# Reciever_Schematic.net
KiCad netlist of a schematic drawn in Altium Designer
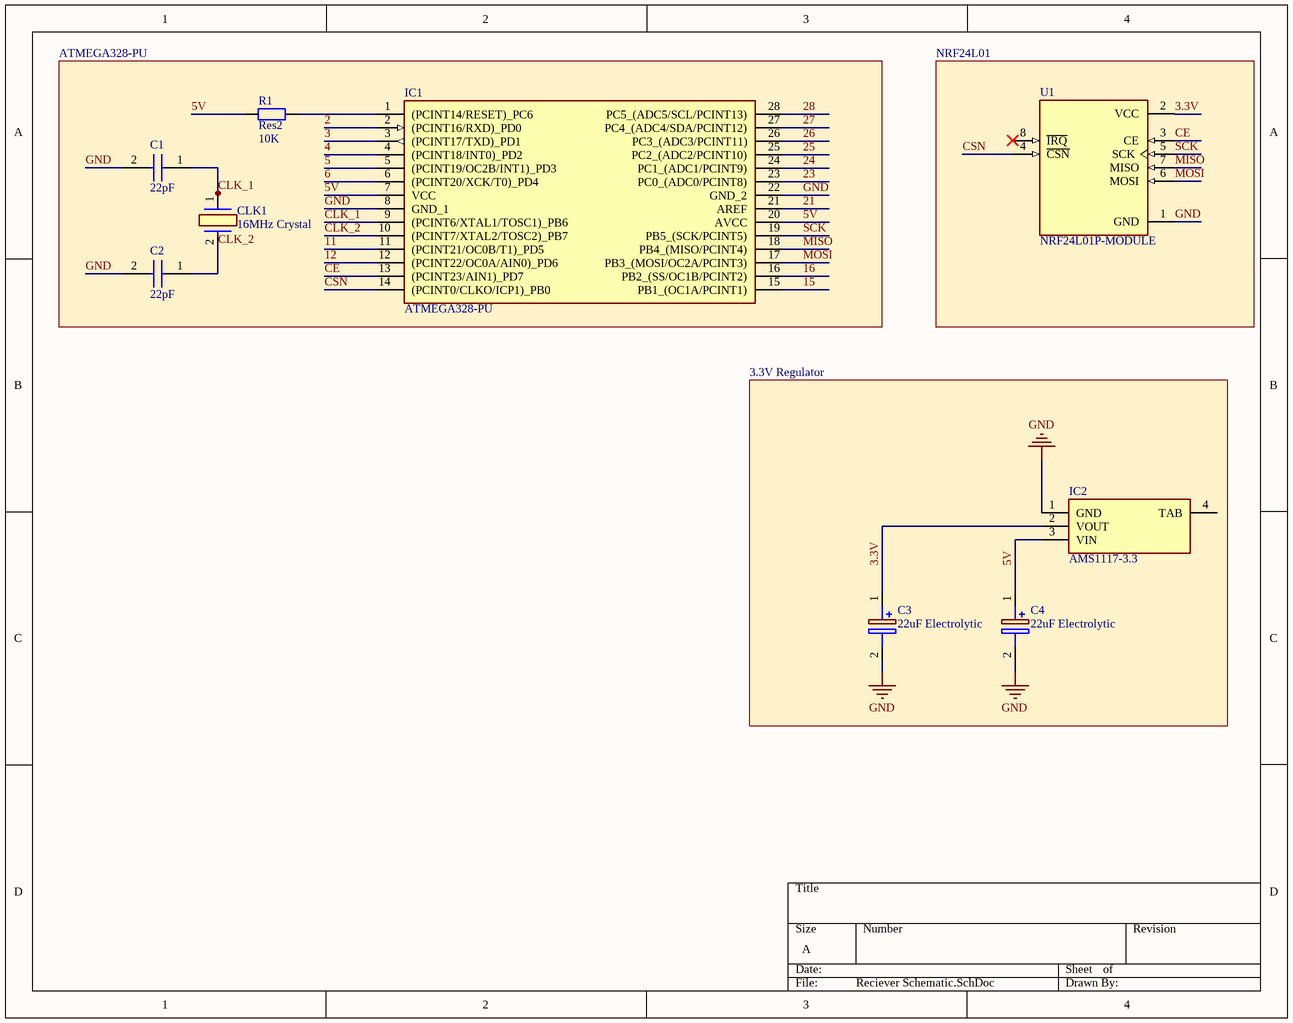
[diagram p0: Reciever Schematic.SchDoc]

(export (version "E")
  (design (tool "Eeschema 10.0.6"))
  (components
    (comp (ref "C1")
      (value "22pF")
      (footprint "SamacSys:S220K25SL0N63L6R")
      (description "Capacitor Ceramic THT")
      (fields
        (field (name "MANUFACTURER_PART_NUMBER") "S220K25SL0N63L6R")
        (field (name "MOUSER PART NUMBER") "594-S220K25SL0N63L6R")
      )
      (libsource (lib "*") (part "S220K25SL0N63L6R"))
    )
    (comp (ref "C2")
      (value "22pF")
      (footprint "SamacSys:S220K25SL0N63L6R")
      (description "Capacitor Ceramic THT")
      (fields
        (field (name "MANUFACTURER_PART_NUMBER") "S220K25SL0N63L6R")
        (field (name "MOUSER PART NUMBER") "594-S220K25SL0N63L6R")
      )
      (libsource (lib "*") (part "S220K25SL0N63L6R"))
    )
    (comp (ref "C3")
      (value "22uF Electrolytic")
      (footprint "SamacSys:CAPPRD250W55D630H1220")
      (description "Capacitor Polarised")
      (fields (field (name "MANUFACTURER_PART_NUMBER") "ECA1EEN220"))
      (libsource (lib "*") (part "ECA1EEN220"))
    )
    (comp (ref "C4")
      (value "22uF Electrolytic")
      (footprint "SamacSys:CAPPRD250W55D630H1220")
      (description "Capacitor Polarised")
      (fields (field (name "MANUFACTURER_PART_NUMBER") "ECA1EEN220"))
      (libsource (lib "*") (part "ECA1EEN220"))
    )
    (comp (ref "CLK1")
      (value "16MHz Crystal")
      (footprint "SamacSys:LFXTAL036391Bulk")
      (description "Crystal or Oscillator")
      (fields
        (field (name "MANUFACTURER_PART_NUMBER") "LFXTAL036391Bulk")
        (field (name "MOUSER PART NUMBER") "449-LFXTAL036391BULK")
      )
      (libsource (lib "*") (part "LFXTAL036391Bulk"))
    )
    (comp (ref "IC1")
      (value "ATMEGA328-PU")
      (footprint "SamacSys:DIP1016W53P254L3468H457Q28N")
      (description "Integrated Circuit")
      (fields (field (name "MOUSER PART NUMBER") "556-ATMEGA328-PU"))
      (libsource (lib "*") (part "ATMEGA328-PU"))
    )
    (comp (ref "IC2")
      (value "AMS1117-3.3")
      (footprint "SamacSys:SOT229P700X180-4N")
      (description "Integrated Circuit")
      (libsource (lib "*") (part "AMS1117-3.3"))
    )
    (comp (ref "R1")
      (value "Res2")
      (footprint "AXIAL-0.4")
      (description "Resistor")
      (fields (field (name "ALTIUM_VALUE") "10K") (field (name "PUBLISHER") "Altium Limited"))
      (libsource (lib "Miscellaneous Devices") (part "Res2"))
    )
    (comp (ref "U1")
      (value "NRF24L01P-MODULE")
      (footprint "XCVR_NRF24L01P-MODULE-PCB")
      (description "- Transceiver For Use With nRF24L01+")
      (fields (field (name "MP") "NRF24L01P-MODULE-PCB") (field (name "MF") "Nordic Semiconductor"))
      (libsource (lib "NRF24L01P-MODULE-PCB") (part "NRF24L01P-MODULE-PCB"))
    )
  )
  (nets
    (net (code "1") (name "/2") (class "Default")
      (node (ref "IC1") (pin "2") (pinfunction "(PCINT16/RXD)_PD0_2") (pintype "input"))
    )
    (net (code "2") (name "/3") (class "Default")
      (node (ref "IC1") (pin "3") (pinfunction "(PCINT17/TXD)_PD1_3") (pintype "output"))
    )
    (net (code "3") (name "/3.3V") (class "Default")
      (node (ref "C3") (pin "1") (pinfunction "+_1") (pintype "passive"))
      (node (ref "IC2") (pin "2") (pinfunction "VOUT_2") (pintype "passive"))
      (node (ref "U1") (pin "2") (pinfunction "VCC_2") (pintype "power_in"))
    )
    (net (code "4") (name "/4") (class "Default")
      (node (ref "IC1") (pin "4") (pinfunction "(PCINT18/INT0)_PD2_4") (pintype "passive"))
    )
    (net (code "5") (name "/5") (class "Default")
      (node (ref "IC1") (pin "5") (pinfunction "(PCINT19/OC2B/INT1)_PD3_5") (pintype "passive"))
    )
    (net (code "6") (name "/5V") (class "Default")
      (node (ref "C4") (pin "1") (pinfunction "+_1") (pintype "passive"))
      (node (ref "IC1") (pin "20") (pinfunction "AVCC_20") (pintype "power_in"))
      (node (ref "IC1") (pin "7") (pinfunction "VCC_7") (pintype "power_in"))
      (node (ref "IC2") (pin "3") (pinfunction "VIN_3") (pintype "passive"))
      (node (ref "R1") (pin "1") (pinfunction "1_1") (pintype "passive"))
    )
    (net (code "7") (name "/6") (class "Default")
      (node (ref "IC1") (pin "6") (pinfunction "(PCINT20/XCK/T0)_PD4_6") (pintype "passive"))
    )
    (net (code "8") (name "/11") (class "Default")
      (node (ref "IC1") (pin "11") (pinfunction "(PCINT21/OC0B/T1)_PD5_11") (pintype "passive"))
    )
    (net (code "9") (name "/12") (class "Default")
      (node (ref "IC1") (pin "12") (pinfunction "(PCINT22/OC0A/AIN0)_PD6_12") (pintype "passive"))
    )
    (net (code "10") (name "/15") (class "Default")
      (node (ref "IC1") (pin "15") (pinfunction "PB1_(OC1A/PCINT1)_15") (pintype "passive"))
    )
    (net (code "11") (name "/16") (class "Default")
      (node (ref "IC1") (pin "16") (pinfunction "PB2_(SS/OC1B/PCINT2)_16") (pintype "passive"))
    )
    (net (code "12") (name "/21") (class "Default")
      (node (ref "IC1") (pin "21") (pinfunction "AREF_21") (pintype "passive"))
    )
    (net (code "13") (name "/23") (class "Default")
      (node (ref "IC1") (pin "23") (pinfunction "PC0_(ADC0/PCINT8)_23") (pintype "passive"))
    )
    (net (code "14") (name "/24") (class "Default")
      (node (ref "IC1") (pin "24") (pinfunction "PC1_(ADC1/PCINT9)_24") (pintype "passive"))
    )
    (net (code "15") (name "/25") (class "Default")
      (node (ref "IC1") (pin "25") (pinfunction "PC2_(ADC2/PCINT10)_25") (pintype "passive"))
    )
    (net (code "16") (name "/26") (class "Default")
      (node (ref "IC1") (pin "26") (pinfunction "PC3_(ADC3/PCINT11)_26") (pintype "passive"))
    )
    (net (code "17") (name "/27") (class "Default")
      (node (ref "IC1") (pin "27") (pinfunction "PC4_(ADC4/SDA/PCINT12)_27") (pintype "passive"))
    )
    (net (code "18") (name "/28") (class "Default")
      (node (ref "IC1") (pin "28") (pinfunction "PC5_(ADC5/SCL/PCINT13)_28") (pintype "passive"))
    )
    (net (code "19") (name "/CE") (class "Default")
      (node (ref "IC1") (pin "13") (pinfunction "(PCINT23/AIN1)_PD7_13") (pintype "passive"))
      (node (ref "U1") (pin "3") (pinfunction "CE_3") (pintype "input"))
    )
    (net (code "20") (name "/CLK_1") (class "Default")
      (node (ref "C1") (pin "1") (pinfunction "1_1") (pintype "passive"))
      (node (ref "CLK1") (pin "1") (pinfunction "CRYSTAL_1_1") (pintype "passive"))
      (node (ref "IC1") (pin "9") (pinfunction "(PCINT6/XTAL1/TOSC1)_PB6_9") (pintype "passive"))
    )
    (net (code "21") (name "/CLK_2") (class "Default")
      (node (ref "C2") (pin "1") (pinfunction "1_1") (pintype "passive"))
      (node (ref "CLK1") (pin "2") (pinfunction "CRYSTAL_2_2") (pintype "passive"))
      (node (ref "IC1") (pin "10") (pinfunction "(PCINT7/XTAL2/TOSC2)_PB7_10") (pintype "passive"))
    )
    (net (code "22") (name "/CSN") (class "Default")
      (node (ref "IC1") (pin "14") (pinfunction "(PCINT0/CLKO/ICP1)_PB0_14") (pintype "passive"))
      (node (ref "U1") (pin "4") (pinfunction "~{CSN}_4") (pintype "input"))
    )
    (net (code "23") (name "/MISO") (class "Default")
      (node (ref "IC1") (pin "18") (pinfunction "PB4_(MISO/PCINT4)_18") (pintype "passive"))
      (node (ref "U1") (pin "7") (pinfunction "MISO_7") (pintype "input"))
    )
    (net (code "24") (name "/MOSI") (class "Default")
      (node (ref "IC1") (pin "17") (pinfunction "PB3_(MOSI/OC2A/PCINT3)_17") (pintype "passive"))
      (node (ref "U1") (pin "6") (pinfunction "MOSI_6") (pintype "input"))
    )
    (net (code "25") (name "/SCK") (class "Default")
      (node (ref "IC1") (pin "19") (pinfunction "PB5_(SCK/PCINT5)_19") (pintype "passive"))
      (node (ref "U1") (pin "5") (pinfunction "SCK_5") (pintype "input"))
    )
    (net (code "26") (name "GND") (class "Default")
      (node (ref "C1") (pin "2") (pinfunction "2_2") (pintype "passive"))
      (node (ref "C2") (pin "2") (pinfunction "2_2") (pintype "passive"))
      (node (ref "C3") (pin "2") (pinfunction "-_2") (pintype "passive"))
      (node (ref "C4") (pin "2") (pinfunction "-_2") (pintype "passive"))
      (node (ref "IC1") (pin "22") (pinfunction "GND_2_22") (pintype "power_in"))
      (node (ref "IC1") (pin "8") (pinfunction "GND_1_8") (pintype "power_in"))
      (node (ref "IC2") (pin "1") (pinfunction "GND_1") (pintype "passive"))
      (node (ref "U1") (pin "1") (pinfunction "GND_1") (pintype "power_in"))
    )
    (net (code "27") (name "Net-(IC1-(PCINT14{slash}RESET)_PC6)") (class "Default")
      (node (ref "IC1") (pin "1") (pinfunction "(PCINT14/RESET)_PC6_1") (pintype "passive"))
      (node (ref "R1") (pin "2") (pinfunction "2_2") (pintype "passive"))
    )
    (net (code "28") (name "unconnected-(IC2-TAB-Pad4)") (class "Default")
      (node (ref "IC2") (pin "4") (pinfunction "TAB_4") (pintype "passive"))
    )
    (net (code "29") (name "unconnected-(U1-~{IRQ}-Pad8)") (class "Default")
      (node (ref "U1") (pin "8") (pinfunction "~{IRQ}_8") (pintype "input+no_connect"))
    )
  )
)
